# BW1098OAK_Connector.net
KiCad netlist of a schematic drawn in Altium Designer
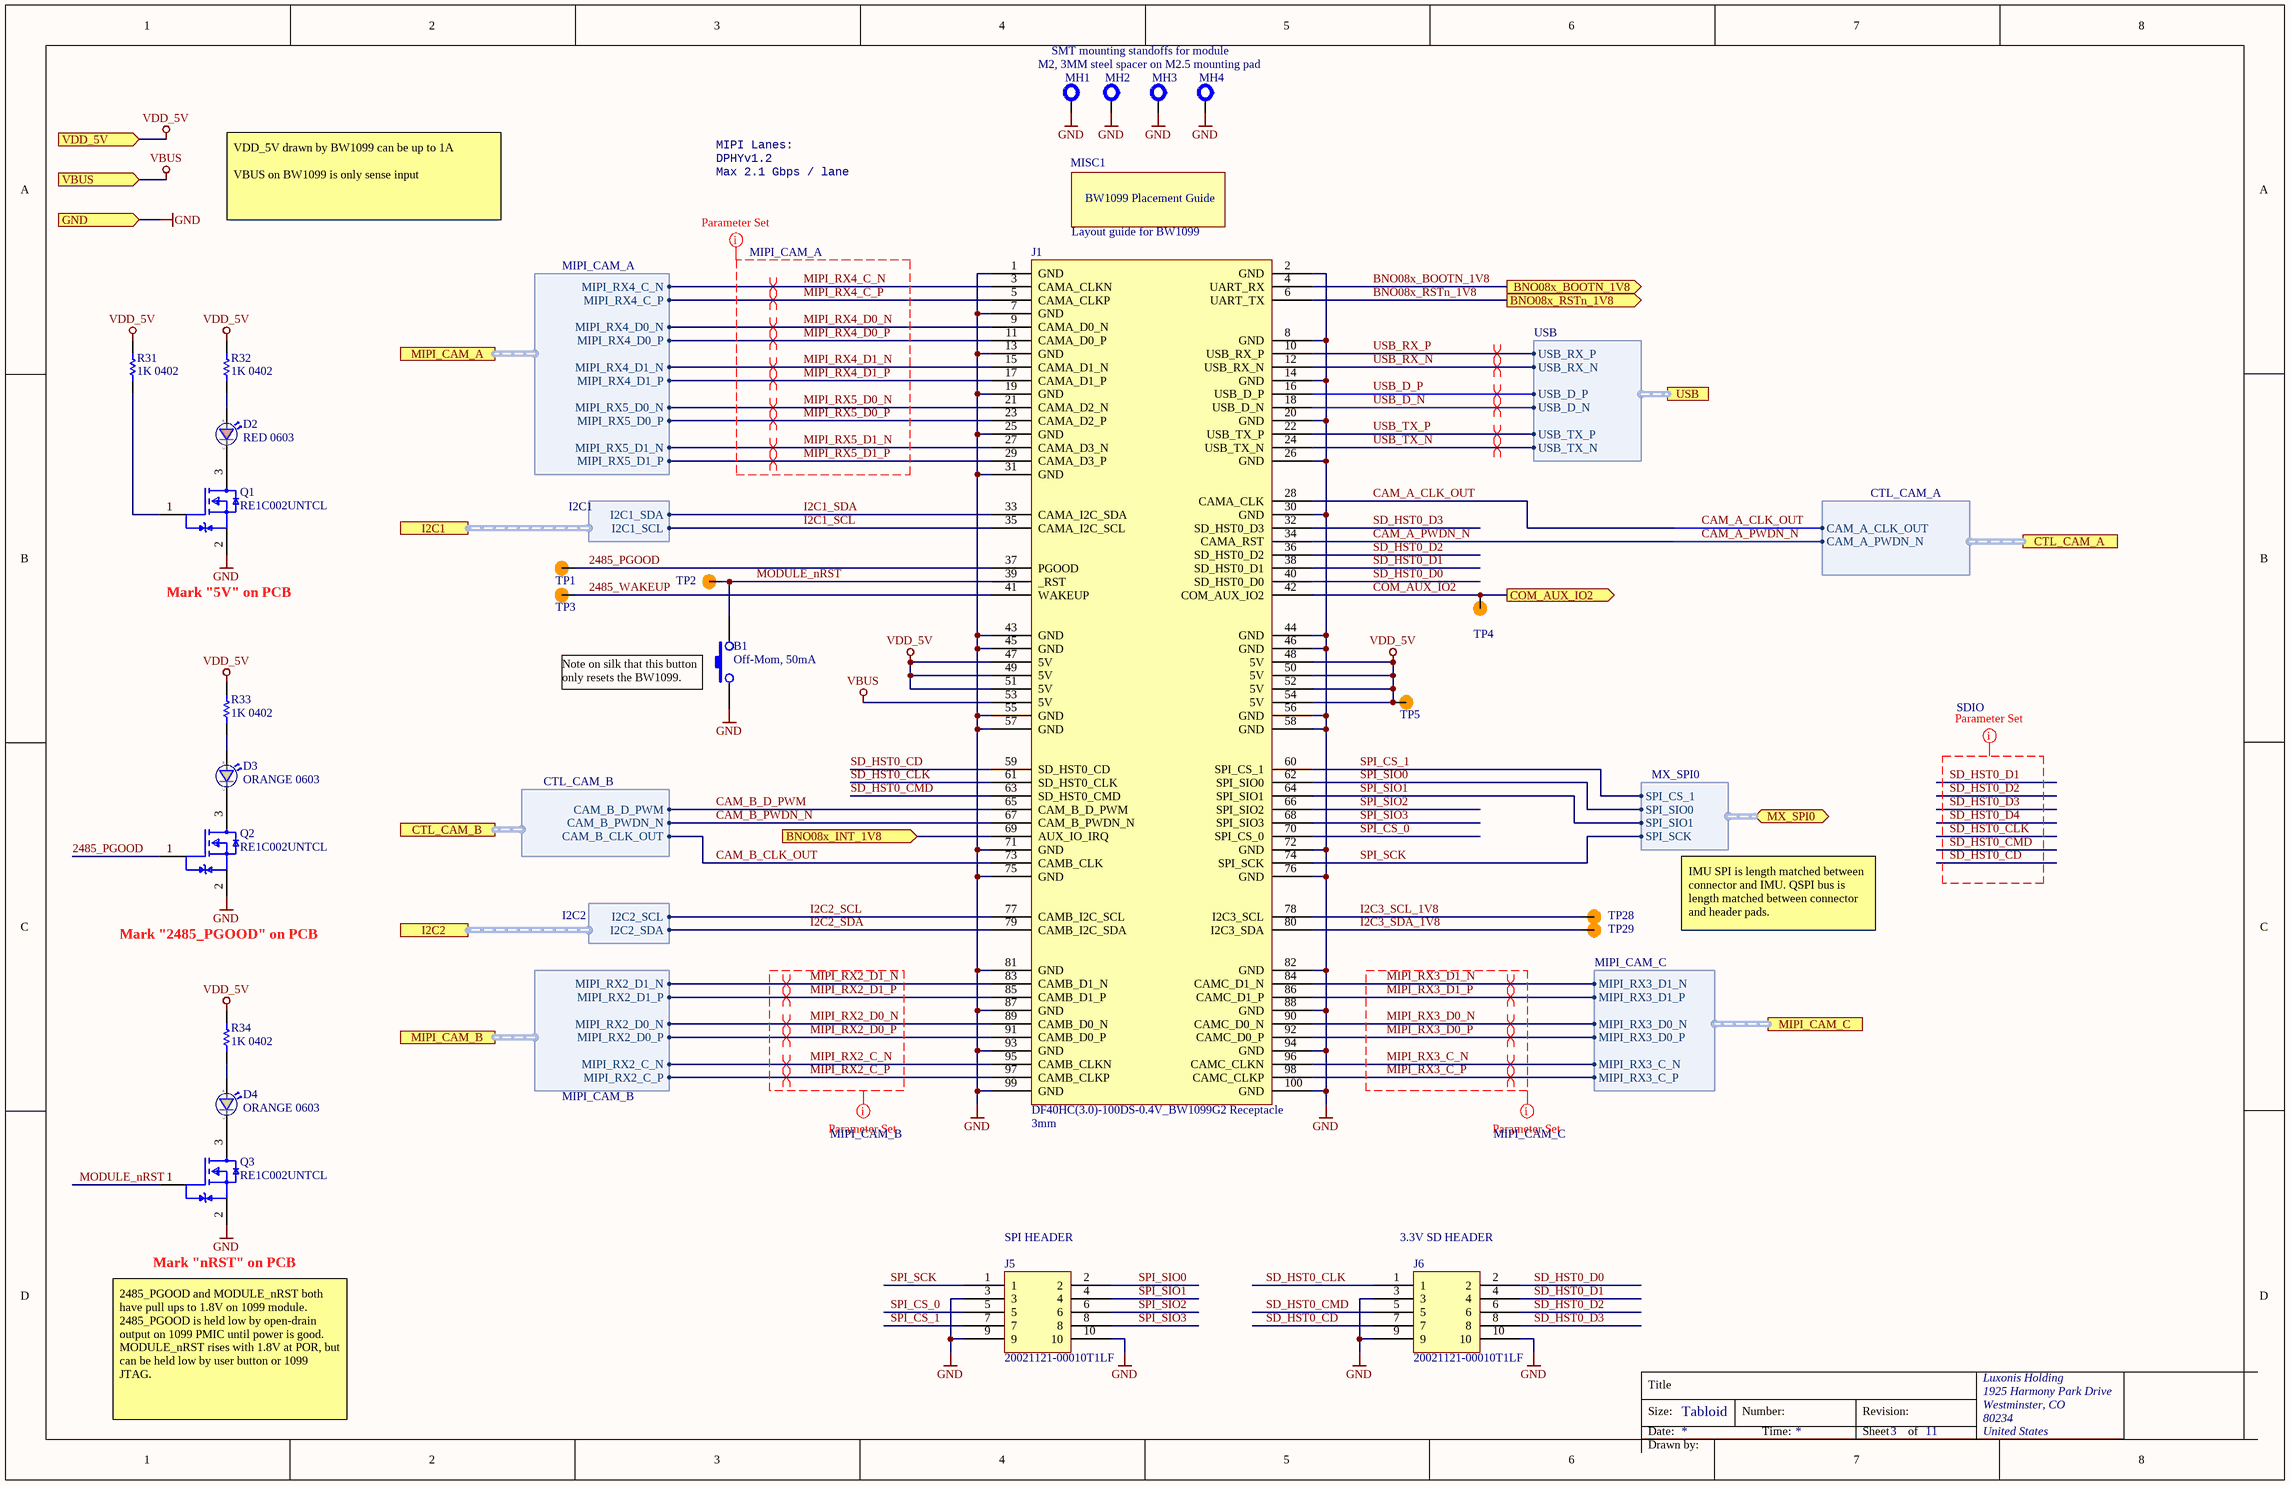
[diagram p0: BW1098OAK_Connector.SchDoc]

(export (version "E")
  (design (tool "Eeschema 10.0.6"))
  (components
    (comp (ref "B1")
      (value "Off-Mom, 50mA")
      (footprint "LuxonisMaster:DTSM-32N-V")
      (description "SWITCH TACTILE SMT 3.5mm * 6mm , brown 160gf")
      (libsource (lib "LuxonisMaster") (part "DTSM-32N-V"))
    )
    (comp (ref "D2")
      (value "RED 0603")
      (footprint "LuxonisMaster:SML_D1xx8W")
      (description "LED RED DIFFUSED 0603 SMD Red 620nm LED Indication - Discrete 2.2V 0603 (1608 Metric)")
      (libsource (lib "LuxonisMaster") (part "SML-D12U8WT86"))
    )
    (comp (ref "D3")
      (value "ORANGE 0603")
      (footprint "LuxonisMaster:SML_D1xx8W")
      (description "LED ORANGE DIFFUSED 0603 SMD Orange 605nm LED Indication - Discrete 2.2V 0603 (1608 Metric)")
      (libsource (lib "LuxonisMaster") (part "SML-D12D8WT86"))
    )
    (comp (ref "D4")
      (value "ORANGE 0603")
      (footprint "LuxonisMaster:SML_D1xx8W")
      (description "LED ORANGE DIFFUSED 0603 SMD Orange 605nm LED Indication - Discrete 2.2V 0603 (1608 Metric)")
      (libsource (lib "LuxonisMaster") (part "SML-D12D8WT86"))
    )
    (comp (ref "J1")
      (value "DF40HC(3.0)-100DS-0.4V_BW1099G2 Receptacle")
      (footprint "LuxonisMaster:DF40HC-3.0-100DS-0.4V_minpad")
      (description "CONN RCPT 100POS 0.4MM SMD GOLD")
      (fields (field (name "MATED STACKING HEIGHT") "3mm"))
      (libsource (lib "LuxonisMaster") (part "DF40HC(3.0)-100DS-0.4V_BW1099_G2"))
    )
    (comp (ref "J5")
      (value "20021121-00010T1LF")
      (footprint "LuxonisMaster:20021121-00010T1LF")
      (description "CONN HEADER SMD 10POS 1.27MM")
      (libsource (lib "LuxonisMaster") (part "20021121-00010T1LF"))
    )
    (comp (ref "J6")
      (value "20021121-00010T1LF")
      (footprint "LuxonisMaster:20021121-00010T1LF")
      (description "CONN HEADER SMD 10POS 1.27MM")
      (libsource (lib "LuxonisMaster") (part "20021121-00010T1LF"))
    )
    (comp (ref "MH1")
      (value "M2, 3MM steel spacer on M2.5 mounting pad")
      (footprint "LuxonisMaster:9774030243R w/ bottom pad")
      (description "MP ROUND STANDOFF M2X0.4 STEEL 3MM")
      (libsource (lib "LuxonisMaster") (part "9774030243R"))
    )
    (comp (ref "MH2")
      (value "M2, 3MM steel spacer on M2.5 mounting pad")
      (footprint "LuxonisMaster:9774030243R w/ bottom pad")
      (description "MP ROUND STANDOFF M2X0.4 STEEL 3MM")
      (libsource (lib "LuxonisMaster") (part "9774030243R"))
    )
    (comp (ref "MH3")
      (value "M2, 3MM steel spacer on M2.5 mounting pad")
      (footprint "LuxonisMaster:9774030243R w/ bottom pad")
      (description "MP ROUND STANDOFF M2X0.4 STEEL 3MM")
      (libsource (lib "LuxonisMaster") (part "9774030243R"))
    )
    (comp (ref "MH4")
      (value "M2, 3MM steel spacer on M2.5 mounting pad")
      (footprint "LuxonisMaster:9774030243R w/ bottom pad")
      (description "MP ROUND STANDOFF M2X0.4 STEEL 3MM")
      (libsource (lib "LuxonisMaster") (part "9774030243R"))
    )
    (comp (ref "MISC1")
      (value "Layout guide for BW1099")
      (footprint "BW1099_R3_KTHSNF_Footprint")
      (description "MISC - Use for aligning BW1099 mount")
      (libsource (lib "LuxonisMaster") (part "BW1099_Footprint"))
    )
    (comp (ref "Q1")
      (value "RE1C002UNTCL")
      (footprint "LuxonisMaster:RE1C002UNTCL")
      (description "MOSFET N-CH 20V 0.2A EMT3")
      (libsource (lib "LuxonisMaster") (part "RE1C002UNTCL"))
    )
    (comp (ref "Q2")
      (value "RE1C002UNTCL")
      (footprint "LuxonisMaster:RE1C002UNTCL")
      (description "MOSFET N-CH 20V 0.2A EMT3")
      (libsource (lib "LuxonisMaster") (part "RE1C002UNTCL"))
    )
    (comp (ref "Q3")
      (value "RE1C002UNTCL")
      (footprint "LuxonisMaster:RE1C002UNTCL")
      (description "MOSFET N-CH 20V 0.2A EMT3")
      (libsource (lib "LuxonisMaster") (part "RE1C002UNTCL"))
    )
    (comp (ref "R31")
      (value "1K 0402")
      (footprint "RES_Altium_Vault_Generic:RESC0402(1005)_L")
      (fields (field (name "TOLERANCE") "1%"))
      (libsource (lib "LuxonisMaster") (part "RC0402FR-071KL"))
    )
    (comp (ref "R32")
      (value "1K 0402")
      (footprint "RES_Altium_Vault_Generic:RESC0402(1005)_L")
      (fields (field (name "TOLERANCE") "1%"))
      (libsource (lib "LuxonisMaster") (part "RC0402FR-071KL"))
    )
    (comp (ref "R33")
      (value "1K 0402")
      (footprint "RES_Altium_Vault_Generic:RESC0402(1005)_L")
      (fields (field (name "TOLERANCE") "1%"))
      (libsource (lib "LuxonisMaster") (part "RC0402FR-071KL"))
    )
    (comp (ref "R34")
      (value "1K 0402")
      (footprint "RES_Altium_Vault_Generic:RESC0402(1005)_L")
      (fields (field (name "TOLERANCE") "1%"))
      (libsource (lib "LuxonisMaster") (part "RC0402FR-071KL"))
    )
    (comp (ref "TP1")
      (value "TP100_200_NS")
      (footprint "LuxonisMaster:TP100_200_NS")
      (libsource (lib "LuxonisMaster") (part "TEST_POINT"))
    )
    (comp (ref "TP2")
      (value "TP100_200_NS")
      (footprint "LuxonisMaster:TP100_200_NS")
      (libsource (lib "LuxonisMaster") (part "TEST_POINT"))
    )
    (comp (ref "TP3")
      (value "TP100_200_NS")
      (footprint "LuxonisMaster:TP100_200_NS")
      (libsource (lib "LuxonisMaster") (part "TEST_POINT"))
    )
    (comp (ref "TP4")
      (value "TP100_200_NS")
      (footprint "LuxonisMaster:TP100_200_NS")
      (libsource (lib "LuxonisMaster") (part "TEST_POINT"))
    )
    (comp (ref "TP5")
      (value "TP100_200_NS")
      (footprint "LuxonisMaster:TP100_200_NS")
      (libsource (lib "LuxonisMaster") (part "TEST_POINT"))
    )
    (comp (ref "TP28")
      (value "TP100_200_NS")
      (footprint "LuxonisMaster:TP100_200_NS")
      (libsource (lib "LuxonisMaster") (part "TEST_POINT"))
    )
    (comp (ref "TP29")
      (value "TP100_200_NS")
      (footprint "LuxonisMaster:TP100_200_NS")
      (libsource (lib "LuxonisMaster") (part "TEST_POINT"))
    )
  )
  (nets
    (net (code "10") (name "/2485_PGOOD") (class "Default")
      (node (ref "J1") (pin "37") (pinfunction "PGOOD_37") (pintype "passive"))
      (node (ref "Q2") (pin "1") (pinfunction "Gate_1") (pintype "passive"))
      (node (ref "TP1") (pin "1") (pintype "passive"))
    )
    (net (code "11") (name "/2485_WAKEUP") (class "Default")
      (node (ref "J1") (pin "41") (pinfunction "WAKEUP_41") (pintype "passive"))
      (node (ref "TP3") (pin "1") (pintype "passive"))
    )
    (net (code "12") (name "/BNO08x_BOOTN_1V8") (class "Default")
      (node (ref "J1") (pin "4") (pinfunction "UART_RX_4") (pintype "passive"))
    )
    (net (code "13") (name "/BNO08x_INT_1V8") (class "Default")
      (node (ref "J1") (pin "69") (pinfunction "AUX_IO_IRQ_69") (pintype "passive"))
    )
    (net (code "14") (name "/BNO08x_RSTn_1V8") (class "Default")
      (node (ref "J1") (pin "6") (pinfunction "UART_TX_6") (pintype "passive"))
    )
    (net (code "15") (name "/CAM_A_CLK_OUT") (class "Default")
      (node (ref "J1") (pin "28") (pinfunction "CAMA_CLK_28") (pintype "passive"))
    )
    (net (code "16") (name "/CAM_A_PWDN_N") (class "Default")
      (node (ref "J1") (pin "34") (pinfunction "CAMA_RST_34") (pintype "passive"))
    )
    (net (code "17") (name "/CAM_B_CLK_OUT") (class "Default")
      (node (ref "J1") (pin "73") (pinfunction "CAMB_CLK_73") (pintype "passive"))
    )
    (net (code "18") (name "/CAM_B_D_PWM") (class "Default")
      (node (ref "J1") (pin "65") (pinfunction "CAM_B_D_PWM_65") (pintype "passive"))
    )
    (net (code "19") (name "/CAM_B_PWDN_N") (class "Default")
      (node (ref "J1") (pin "67") (pinfunction "CAM_B_PWDN_N_67") (pintype "passive"))
    )
    (net (code "20") (name "/COM_AUX_IO2") (class "Default")
      (node (ref "J1") (pin "42") (pinfunction "COM_AUX_IO2_42") (pintype "passive"))
      (node (ref "TP4") (pin "1") (pintype "passive"))
    )
    (net (code "21") (name "/I2C1_SCL") (class "Default")
      (node (ref "J1") (pin "35") (pinfunction "CAMA_I2C_SCL_35") (pintype "passive"))
    )
    (net (code "22") (name "/I2C1_SDA") (class "Default")
      (node (ref "J1") (pin "33") (pinfunction "CAMA_I2C_SDA_33") (pintype "passive"))
    )
    (net (code "23") (name "/I2C2_SCL") (class "Default")
      (node (ref "J1") (pin "77") (pinfunction "CAMB_I2C_SCL_77") (pintype "passive"))
    )
    (net (code "24") (name "/I2C2_SDA") (class "Default")
      (node (ref "J1") (pin "79") (pinfunction "CAMB_I2C_SDA_79") (pintype "passive"))
    )
    (net (code "25") (name "/I2C3_SCL_1V8") (class "Default")
      (node (ref "J1") (pin "78") (pinfunction "I2C3_SCL_78") (pintype "passive"))
      (node (ref "TP28") (pin "1") (pintype "passive"))
    )
    (net (code "26") (name "/I2C3_SDA_1V8") (class "Default")
      (node (ref "J1") (pin "80") (pinfunction "I2C3_SDA_80") (pintype "passive"))
      (node (ref "TP29") (pin "1") (pintype "passive"))
    )
    (net (code "27") (name "/MIPI_RX2_C_N") (class "Default")
      (node (ref "J1") (pin "95") (pinfunction "CAMB_CLKN_95") (pintype "passive"))
    )
    (net (code "28") (name "/MIPI_RX2_C_P") (class "Default")
      (node (ref "J1") (pin "97") (pinfunction "CAMB_CLKP_97") (pintype "passive"))
    )
    (net (code "29") (name "/MIPI_RX2_D0_N") (class "Default")
      (node (ref "J1") (pin "89") (pinfunction "CAMB_D0_N_89") (pintype "passive"))
    )
    (net (code "30") (name "/MIPI_RX2_D0_P") (class "Default")
      (node (ref "J1") (pin "91") (pinfunction "CAMB_D0_P_91") (pintype "passive"))
    )
    (net (code "31") (name "/MIPI_RX2_D1_N") (class "Default")
      (node (ref "J1") (pin "83") (pinfunction "CAMB_D1_N_83") (pintype "passive"))
    )
    (net (code "32") (name "/MIPI_RX2_D1_P") (class "Default")
      (node (ref "J1") (pin "85") (pinfunction "CAMB_D1_P_85") (pintype "passive"))
    )
    (net (code "33") (name "/MIPI_RX3_C_N") (class "Default")
      (node (ref "J1") (pin "96") (pinfunction "CAMC_CLKN_96") (pintype "passive"))
    )
    (net (code "34") (name "/MIPI_RX3_C_P") (class "Default")
      (node (ref "J1") (pin "98") (pinfunction "CAMC_CLKP_98") (pintype "passive"))
    )
    (net (code "35") (name "/MIPI_RX3_D0_N") (class "Default")
      (node (ref "J1") (pin "90") (pinfunction "CAMC_D0_N_90") (pintype "passive"))
    )
    (net (code "36") (name "/MIPI_RX3_D0_P") (class "Default")
      (node (ref "J1") (pin "92") (pinfunction "CAMC_D0_P_92") (pintype "passive"))
    )
    (net (code "37") (name "/MIPI_RX3_D1_N") (class "Default")
      (node (ref "J1") (pin "84") (pinfunction "CAMC_D1_N_84") (pintype "passive"))
    )
    (net (code "38") (name "/MIPI_RX3_D1_P") (class "Default")
      (node (ref "J1") (pin "86") (pinfunction "CAMC_D1_P_86") (pintype "passive"))
    )
    (net (code "39") (name "/MIPI_RX4_C_N") (class "Default")
      (node (ref "J1") (pin "3") (pinfunction "CAMA_CLKN_3") (pintype "passive"))
    )
    (net (code "40") (name "/MIPI_RX4_C_P") (class "Default")
      (node (ref "J1") (pin "5") (pinfunction "CAMA_CLKP_5") (pintype "passive"))
    )
    (net (code "41") (name "/MIPI_RX4_D0_N") (class "Default")
      (node (ref "J1") (pin "9") (pinfunction "CAMA_D0_N_9") (pintype "passive"))
    )
    (net (code "42") (name "/MIPI_RX4_D0_P") (class "Default")
      (node (ref "J1") (pin "11") (pinfunction "CAMA_D0_P_11") (pintype "passive"))
    )
    (net (code "43") (name "/MIPI_RX4_D1_N") (class "Default")
      (node (ref "J1") (pin "15") (pinfunction "CAMA_D1_N_15") (pintype "passive"))
    )
    (net (code "44") (name "/MIPI_RX4_D1_P") (class "Default")
      (node (ref "J1") (pin "17") (pinfunction "CAMA_D1_P_17") (pintype "passive"))
    )
    (net (code "45") (name "/MIPI_RX5_D0_N") (class "Default")
      (node (ref "J1") (pin "21") (pinfunction "CAMA_D2_N_21") (pintype "passive"))
    )
    (net (code "46") (name "/MIPI_RX5_D0_P") (class "Default")
      (node (ref "J1") (pin "23") (pinfunction "CAMA_D2_P_23") (pintype "passive"))
    )
    (net (code "47") (name "/MIPI_RX5_D1_N") (class "Default")
      (node (ref "J1") (pin "27") (pinfunction "CAMA_D3_N_27") (pintype "passive"))
    )
    (net (code "48") (name "/MIPI_RX5_D1_P") (class "Default")
      (node (ref "J1") (pin "29") (pinfunction "CAMA_D3_P_29") (pintype "passive"))
    )
    (net (code "49") (name "/MODULE_nRST") (class "Default")
      (node (ref "B1") (pin "2") (pinfunction "2_2") (pintype "passive"))
      (node (ref "J1") (pin "39") (pinfunction "_RST_39") (pintype "passive"))
      (node (ref "Q3") (pin "1") (pinfunction "Gate_1") (pintype "passive"))
      (node (ref "TP2") (pin "1") (pintype "passive"))
    )
    (net (code "50") (name "/SD_HST0_CD") (class "Default")
      (node (ref "J1") (pin "59") (pinfunction "SD_HST0_CD_59") (pintype "passive"))
      (node (ref "J6") (pin "7") (pinfunction "7_7") (pintype "passive"))
    )
    (net (code "51") (name "/SD_HST0_CLK") (class "Default")
      (node (ref "J1") (pin "61") (pinfunction "SD_HST0_CLK_61") (pintype "passive"))
      (node (ref "J6") (pin "1") (pinfunction "1_1") (pintype "passive"))
    )
    (net (code "52") (name "/SD_HST0_CMD") (class "Default")
      (node (ref "J1") (pin "63") (pinfunction "SD_HST0_CMD_63") (pintype "passive"))
      (node (ref "J6") (pin "5") (pinfunction "5_5") (pintype "passive"))
    )
    (net (code "53") (name "/SD_HST0_D0") (class "Default")
      (node (ref "J1") (pin "40") (pinfunction "SD_HST0_D0_40") (pintype "passive"))
      (node (ref "J6") (pin "2") (pinfunction "2_2") (pintype "passive"))
    )
    (net (code "54") (name "/SD_HST0_D1") (class "Default")
      (node (ref "J1") (pin "38") (pinfunction "SD_HST0_D1_38") (pintype "passive"))
      (node (ref "J6") (pin "4") (pinfunction "4_4") (pintype "passive"))
    )
    (net (code "55") (name "/SD_HST0_D2") (class "Default")
      (node (ref "J1") (pin "36") (pinfunction "SD_HST0_D2_36") (pintype "passive"))
      (node (ref "J6") (pin "6") (pinfunction "6_6") (pintype "passive"))
    )
    (net (code "56") (name "/SD_HST0_D3") (class "Default")
      (node (ref "J1") (pin "32") (pinfunction "SD_HST0_D3_32") (pintype "passive"))
      (node (ref "J6") (pin "8") (pinfunction "8_8") (pintype "passive"))
    )
    (net (code "58") (name "/SPI_CS_0") (class "Default")
      (node (ref "J1") (pin "70") (pinfunction "SPI_CS_0_70") (pintype "passive"))
      (node (ref "J5") (pin "5") (pinfunction "5_5") (pintype "passive"))
    )
    (net (code "59") (name "/SPI_CS_1") (class "Default")
      (node (ref "J1") (pin "60") (pinfunction "SPI_CS_1_60") (pintype "passive"))
      (node (ref "J5") (pin "7") (pinfunction "7_7") (pintype "passive"))
    )
    (net (code "60") (name "/SPI_SCK") (class "Default")
      (node (ref "J1") (pin "74") (pinfunction "SPI_SCK_74") (pintype "passive"))
      (node (ref "J5") (pin "1") (pinfunction "1_1") (pintype "passive"))
    )
    (net (code "61") (name "/SPI_SIO0") (class "Default")
      (node (ref "J1") (pin "62") (pinfunction "SPI_SIO0_62") (pintype "passive"))
      (node (ref "J5") (pin "2") (pinfunction "2_2") (pintype "passive"))
    )
    (net (code "62") (name "/SPI_SIO1") (class "Default")
      (node (ref "J1") (pin "64") (pinfunction "SPI_SIO1_64") (pintype "passive"))
      (node (ref "J5") (pin "4") (pinfunction "4_4") (pintype "passive"))
    )
    (net (code "63") (name "/SPI_SIO2") (class "Default")
      (node (ref "J1") (pin "66") (pinfunction "SPI_SIO2_66") (pintype "passive"))
      (node (ref "J5") (pin "6") (pinfunction "6_6") (pintype "passive"))
    )
    (net (code "64") (name "/SPI_SIO3") (class "Default")
      (node (ref "J1") (pin "68") (pinfunction "SPI_SIO3_68") (pintype "passive"))
      (node (ref "J5") (pin "8") (pinfunction "8_8") (pintype "passive"))
    )
    (net (code "65") (name "/USB_D_N") (class "Default")
      (node (ref "J1") (pin "18") (pinfunction "USB_D_N_18") (pintype "passive"))
    )
    (net (code "66") (name "/USB_D_P") (class "Default")
      (node (ref "J1") (pin "16") (pinfunction "USB_D_P_16") (pintype "passive"))
    )
    (net (code "67") (name "/USB_RX_N") (class "Default")
      (node (ref "J1") (pin "12") (pinfunction "USB_RX_N_12") (pintype "passive"))
    )
    (net (code "68") (name "/USB_RX_P") (class "Default")
      (node (ref "J1") (pin "10") (pinfunction "USB_RX_P_10") (pintype "passive"))
    )
    (net (code "69") (name "/USB_TX_N") (class "Default")
      (node (ref "J1") (pin "24") (pinfunction "USB_TX_N_24") (pintype "passive"))
    )
    (net (code "70") (name "/USB_TX_P") (class "Default")
      (node (ref "J1") (pin "22") (pinfunction "USB_TX_P_22") (pintype "passive"))
    )
    (net (code "80") (name "GND") (class "Default")
      (node (ref "B1") (pin "1") (pinfunction "1_1") (pintype "passive"))
      (node (ref "J1") (pin "1") (pinfunction "GND_1") (pintype "passive"))
      (node (ref "J1") (pin "100") (pinfunction "GND_100") (pintype "passive"))
      (node (ref "J1") (pin "13") (pinfunction "GND_13") (pintype "passive"))
      (node (ref "J1") (pin "14") (pinfunction "GND_14") (pintype "passive"))
      (node (ref "J1") (pin "19") (pinfunction "GND_19") (pintype "passive"))
      (node (ref "J1") (pin "2") (pinfunction "GND_2") (pintype "passive"))
      (node (ref "J1") (pin "20") (pinfunction "GND_20") (pintype "passive"))
      (node (ref "J1") (pin "25") (pinfunction "GND_25") (pintype "passive"))
      (node (ref "J1") (pin "26") (pinfunction "GND_26") (pintype "passive"))
      (node (ref "J1") (pin "30") (pinfunction "GND_30") (pintype "passive"))
      (node (ref "J1") (pin "31") (pinfunction "GND_31") (pintype "passive"))
      (node (ref "J1") (pin "43") (pinfunction "GND_43") (pintype "passive"))
      (node (ref "J1") (pin "44") (pinfunction "GND_44") (pintype "passive"))
      (node (ref "J1") (pin "45") (pinfunction "GND_45") (pintype "passive"))
      (node (ref "J1") (pin "46") (pinfunction "GND_46") (pintype "passive"))
      (node (ref "J1") (pin "55") (pinfunction "GND_55") (pintype "passive"))
      (node (ref "J1") (pin "56") (pinfunction "GND_56") (pintype "passive"))
      (node (ref "J1") (pin "57") (pinfunction "GND_57") (pintype "passive"))
      (node (ref "J1") (pin "58") (pinfunction "GND_58") (pintype "passive"))
      (node (ref "J1") (pin "7") (pinfunction "GND_7") (pintype "passive"))
      (node (ref "J1") (pin "71") (pinfunction "GND_71") (pintype "passive"))
      (node (ref "J1") (pin "72") (pinfunction "GND_72") (pintype "passive"))
      (node (ref "J1") (pin "75") (pinfunction "GND_75") (pintype "passive"))
      (node (ref "J1") (pin "76") (pinfunction "GND_76") (pintype "passive"))
      (node (ref "J1") (pin "8") (pinfunction "GND_8") (pintype "passive"))
      (node (ref "J1") (pin "81") (pinfunction "GND_81") (pintype "passive"))
      (node (ref "J1") (pin "82") (pinfunction "GND_82") (pintype "passive"))
      (node (ref "J1") (pin "87") (pinfunction "GND_87") (pintype "passive"))
      (node (ref "J1") (pin "88") (pinfunction "GND_88") (pintype "passive"))
      (node (ref "J1") (pin "93") (pinfunction "GND_93") (pintype "passive"))
      (node (ref "J1") (pin "94") (pinfunction "GND_94") (pintype "passive"))
      (node (ref "J1") (pin "99") (pinfunction "GND_99") (pintype "passive"))
      (node (ref "J5") (pin "10") (pinfunction "10_10") (pintype "passive"))
      (node (ref "J5") (pin "3") (pinfunction "3_3") (pintype "passive"))
      (node (ref "J5") (pin "9") (pinfunction "9_9") (pintype "passive"))
      (node (ref "J6") (pin "10") (pinfunction "10_10") (pintype "passive"))
      (node (ref "J6") (pin "3") (pinfunction "3_3") (pintype "passive"))
      (node (ref "J6") (pin "9") (pinfunction "9_9") (pintype "passive"))
      (node (ref "MH1") (pin "1") (pintype "passive"))
      (node (ref "MH2") (pin "1") (pintype "passive"))
      (node (ref "MH3") (pin "1") (pintype "passive"))
      (node (ref "MH4") (pin "1") (pintype "passive"))
      (node (ref "Q1") (pin "2") (pinfunction "Source_2") (pintype "passive"))
      (node (ref "Q2") (pin "2") (pinfunction "Source_2") (pintype "passive"))
      (node (ref "Q3") (pin "2") (pinfunction "Source_2") (pintype "passive"))
    )
    (net (code "81") (name "Net-(D2-A)") (class "Default")
      (node (ref "D2") (pin "2") (pinfunction "A_2") (pintype "passive"))
      (node (ref "R32") (pin "1") (pinfunction "1_1") (pintype "passive"))
    )
    (net (code "82") (name "Net-(D2-C)") (class "Default")
      (node (ref "D2") (pin "1") (pinfunction "C_1") (pintype "passive"))
      (node (ref "Q1") (pin "3") (pinfunction "Drain_3") (pintype "passive"))
    )
    (net (code "83") (name "Net-(D3-A)") (class "Default")
      (node (ref "D3") (pin "2") (pinfunction "A_2") (pintype "passive"))
      (node (ref "R33") (pin "1") (pinfunction "1_1") (pintype "passive"))
    )
    (net (code "84") (name "Net-(D3-C)") (class "Default")
      (node (ref "D3") (pin "1") (pinfunction "C_1") (pintype "passive"))
      (node (ref "Q2") (pin "3") (pinfunction "Drain_3") (pintype "passive"))
    )
    (net (code "85") (name "Net-(D4-A)") (class "Default")
      (node (ref "D4") (pin "2") (pinfunction "A_2") (pintype "passive"))
      (node (ref "R34") (pin "1") (pinfunction "1_1") (pintype "passive"))
    )
    (net (code "86") (name "Net-(D4-C)") (class "Default")
      (node (ref "D4") (pin "1") (pinfunction "C_1") (pintype "passive"))
      (node (ref "Q3") (pin "3") (pinfunction "Drain_3") (pintype "passive"))
    )
    (net (code "87") (name "Net-(Q1-Gate)") (class "Default")
      (node (ref "Q1") (pin "1") (pinfunction "Gate_1") (pintype "passive"))
      (node (ref "R31") (pin "1") (pinfunction "1_1") (pintype "passive"))
    )
    (net (code "88") (name "VBUS") (class "Default")
      (node (ref "J1") (pin "53") (pinfunction "5V_53") (pintype "passive"))
    )
    (net (code "89") (name "VDD_5V") (class "Default")
      (node (ref "J1") (pin "47") (pinfunction "5V_47") (pintype "passive"))
      (node (ref "J1") (pin "48") (pinfunction "5V_48") (pintype "passive"))
      (node (ref "J1") (pin "49") (pinfunction "5V_49") (pintype "passive"))
      (node (ref "J1") (pin "50") (pinfunction "5V_50") (pintype "passive"))
      (node (ref "J1") (pin "51") (pinfunction "5V_51") (pintype "passive"))
      (node (ref "J1") (pin "52") (pinfunction "5V_52") (pintype "passive"))
      (node (ref "J1") (pin "54") (pinfunction "5V_54") (pintype "passive"))
      (node (ref "R31") (pin "2") (pinfunction "2_2") (pintype "passive"))
      (node (ref "R32") (pin "2") (pinfunction "2_2") (pintype "passive"))
      (node (ref "R33") (pin "2") (pinfunction "2_2") (pintype "passive"))
      (node (ref "R34") (pin "2") (pinfunction "2_2") (pintype "passive"))
      (node (ref "TP5") (pin "1") (pintype "passive"))
    )
  )
)
